# jdds-arduino.net
KiCad netlist of a schematic drawn in EAGLE
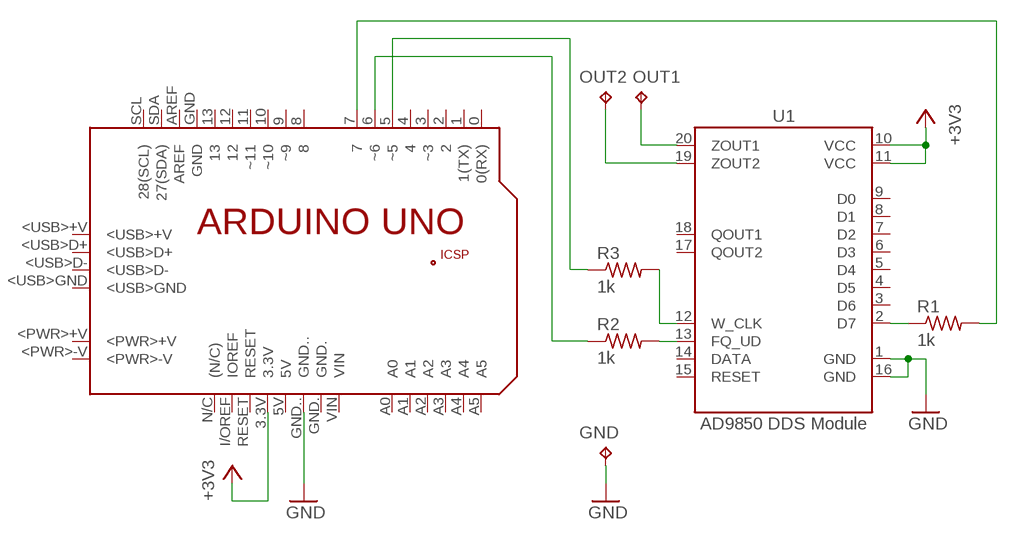
[diagram p0: schematic, sheet 1]

(export (version "E")
  (design (tool "Eeschema 10.0.6"))
  (components
    (comp (ref "GND")
      (value "TPPAD1-20")
      (footprint "eagle-import:P1-20")
      (libsource (lib "eagle-import") (part "TPPAD1-20"))
    )
    (comp (ref "OUT1")
      (value "TPPAD1-20")
      (footprint "eagle-import:P1-20")
      (libsource (lib "eagle-import") (part "TPPAD1-20"))
    )
    (comp (ref "OUT2")
      (value "TPPAD1-20")
      (footprint "eagle-import:P1-20")
      (libsource (lib "eagle-import") (part "TPPAD1-20"))
    )
    (comp (ref "PCB1")
      (value "ARDUINO_UNO")
      (footprint "eagle-import:ARDUINO_UNO")
      (libsource (lib "eagle-import") (part "ARDUINO_UNO"))
    )
    (comp (ref "R1")
      (value "1k")
      (footprint "eagle-import:0207_10")
      (libsource (lib "eagle-import") (part "R-US_0207/10"))
    )
    (comp (ref "R2")
      (value "1k")
      (footprint "eagle-import:0207_10")
      (libsource (lib "eagle-import") (part "R-US_0207/10"))
    )
    (comp (ref "R3")
      (value "1k")
      (footprint "eagle-import:0207_10")
      (libsource (lib "eagle-import") (part "R-US_0207/10"))
    )
    (comp (ref "U1")
      (value "AD9850 DDS Module")
      (footprint "eagle-import:DDS_AD9850")
      (libsource (lib "eagle-import") (part "DDS_MODULE{colon}AD9850DDS_MODULE"))
    )
  )
  (nets
    (net (code "1") (name "+3V3") (class "Default")
      (node (ref "PCB1") (pin "3.3V") (pinfunction "3.3V_3.3V") (pintype "bidirectional"))
      (node (ref "U1") (pin "10") (pinfunction "VCC_10") (pintype "power_in"))
      (node (ref "U1") (pin "11") (pinfunction "VCC_11") (pintype "power_in"))
    )
    (net (code "2") (name "GND") (class "Default")
      (node (ref "GND") (pin "TP") (pinfunction "TP_TP") (pintype "input"))
      (node (ref "PCB1") (pin "GND..") (pinfunction "GND.._GND..") (pintype "bidirectional"))
      (node (ref "U1") (pin "1") (pinfunction "GND_1") (pintype "power_in"))
      (node (ref "U1") (pin "16") (pinfunction "GND_16") (pintype "power_in"))
    )
    (net (code "3") (name "Net-(PCB1-Pad7)") (class "Default")
      (node (ref "PCB1") (pin "7") (pinfunction "7_7") (pintype "bidirectional"))
      (node (ref "R1") (pin "2") (pinfunction "2_2") (pintype "passive"))
    )
    (net (code "4") (name "Net-(PCB1-~{5})") (class "Default")
      (node (ref "PCB1") (pin "5") (pinfunction "~{5}_5") (pintype "bidirectional"))
      (node (ref "R3") (pin "1") (pinfunction "1_1") (pintype "passive"))
    )
    (net (code "5") (name "Net-(PCB1-~{6})") (class "Default")
      (node (ref "PCB1") (pin "6") (pinfunction "~{6}_6") (pintype "bidirectional"))
      (node (ref "R2") (pin "1") (pinfunction "1_1") (pintype "passive"))
    )
    (net (code "6") (name "Net-(U1-D7)") (class "Default")
      (node (ref "R1") (pin "1") (pinfunction "1_1") (pintype "passive"))
      (node (ref "U1") (pin "2") (pinfunction "D7_2") (pintype "input"))
    )
    (net (code "7") (name "Net-(U1-FQ_UD)") (class "Default")
      (node (ref "R2") (pin "2") (pinfunction "2_2") (pintype "passive"))
      (node (ref "U1") (pin "13") (pinfunction "FQ_UD_13") (pintype "input"))
    )
    (net (code "8") (name "Net-(U1-W_CLK)") (class "Default")
      (node (ref "R3") (pin "2") (pinfunction "2_2") (pintype "passive"))
      (node (ref "U1") (pin "12") (pinfunction "W_CLK_12") (pintype "input"))
    )
    (net (code "9") (name "Net-(U1-ZOUT1)") (class "Default")
      (node (ref "OUT1") (pin "TP") (pinfunction "TP_TP") (pintype "input"))
      (node (ref "U1") (pin "20") (pinfunction "ZOUT1_20") (pintype "output"))
    )
    (net (code "10") (name "Net-(U1-ZOUT2)") (class "Default")
      (node (ref "OUT2") (pin "TP") (pinfunction "TP_TP") (pintype "input"))
      (node (ref "U1") (pin "19") (pinfunction "ZOUT2_19") (pintype "output"))
    )
    (net (code "11") (name "unconnected-(PCB1-(N{slash}C)-PadN{slash}C)") (class "Default")
      (node (ref "PCB1") (pin "N/C") (pinfunction "(N/C)_N/C") (pintype "bidirectional"))
    )
    (net (code "12") (name "unconnected-(PCB1-0(RX)-Pad0)") (class "Default")
      (node (ref "PCB1") (pin "0") (pinfunction "0(RX)_0") (pintype "bidirectional"))
    )
    (net (code "13") (name "unconnected-(PCB1-1(TX)-Pad1)") (class "Default")
      (node (ref "PCB1") (pin "1") (pinfunction "1(TX)_1") (pintype "bidirectional"))
    )
    (net (code "14") (name "unconnected-(PCB1-27(SDA)-PadSDA)") (class "Default")
      (node (ref "PCB1") (pin "SDA") (pinfunction "27(SDA)_SDA") (pintype "bidirectional"))
    )
    (net (code "15") (name "unconnected-(PCB1-28(SCL)-PadSCL)") (class "Default")
      (node (ref "PCB1") (pin "SCL") (pinfunction "28(SCL)_SCL") (pintype "bidirectional"))
    )
    (net (code "16") (name "unconnected-(PCB1-IOREF-PadI{slash}OREF)") (class "Default")
      (node (ref "PCB1") (pin "I/OREF") (pinfunction "IOREF_I/OREF") (pintype "bidirectional"))
    )
    (net (code "17") (name "unconnected-(PCB1-Pad+5V)") (class "Default")
      (node (ref "PCB1") (pin "+5V") (pinfunction "+5V_+5V") (pintype "bidirectional"))
    )
    (net (code "18") (name "unconnected-(PCB1-Pad2)") (class "Default")
      (node (ref "PCB1") (pin "2") (pinfunction "2_2") (pintype "bidirectional"))
    )
    (net (code "19") (name "unconnected-(PCB1-Pad4)") (class "Default")
      (node (ref "PCB1") (pin "4") (pinfunction "4_4") (pintype "bidirectional"))
    )
    (net (code "20") (name "unconnected-(PCB1-Pad5V)") (class "Default")
      (node (ref "PCB1") (pin "5V") (pinfunction "5V_5V") (pintype "bidirectional"))
    )
    (net (code "21") (name "unconnected-(PCB1-Pad8)") (class "Default")
      (node (ref "PCB1") (pin "8") (pinfunction "8_8") (pintype "bidirectional"))
    )
    (net (code "22") (name "unconnected-(PCB1-Pad12)") (class "Default")
      (node (ref "PCB1") (pin "12") (pinfunction "12_12") (pintype "bidirectional"))
    )
    (net (code "23") (name "unconnected-(PCB1-Pad13)") (class "Default")
      (node (ref "PCB1") (pin "13") (pinfunction "13_13") (pintype "bidirectional"))
    )
    (net (code "24") (name "unconnected-(PCB1-Pad<PWR>+V)") (class "Default")
      (node (ref "PCB1") (pin "<PWR>+V") (pinfunction "<PWR>+V_<PWR>+V") (pintype "bidirectional"))
    )
    (net (code "25") (name "unconnected-(PCB1-Pad<PWR>-V)") (class "Default")
      (node (ref "PCB1") (pin "<PWR>-V") (pinfunction "<PWR>-V_<PWR>-V") (pintype "bidirectional"))
    )
    (net (code "26") (name "unconnected-(PCB1-Pad<USB>+V)") (class "Default")
      (node (ref "PCB1") (pin "<USB>+V") (pinfunction "<USB>+V_<USB>+V") (pintype "bidirectional"))
    )
    (net (code "27") (name "unconnected-(PCB1-Pad<USB>D+)") (class "Default")
      (node (ref "PCB1") (pin "<USB>D+") (pinfunction "<USB>D+_<USB>D+") (pintype "bidirectional"))
    )
    (net (code "28") (name "unconnected-(PCB1-Pad<USB>D-)") (class "Default")
      (node (ref "PCB1") (pin "<USB>D-") (pinfunction "<USB>D-_<USB>D-") (pintype "bidirectional"))
    )
    (net (code "29") (name "unconnected-(PCB1-Pad<USB>GND)") (class "Default")
      (node (ref "PCB1") (pin "<USB>GND") (pinfunction "<USB>GND_<USB>GND") (pintype "bidirectional"))
    )
    (net (code "30") (name "unconnected-(PCB1-PadA0)") (class "Default")
      (node (ref "PCB1") (pin "A0") (pinfunction "A0_A0") (pintype "bidirectional"))
    )
    (net (code "31") (name "unconnected-(PCB1-PadA1)") (class "Default")
      (node (ref "PCB1") (pin "A1") (pinfunction "A1_A1") (pintype "bidirectional"))
    )
    (net (code "32") (name "unconnected-(PCB1-PadA2)") (class "Default")
      (node (ref "PCB1") (pin "A2") (pinfunction "A2_A2") (pintype "bidirectional"))
    )
    (net (code "33") (name "unconnected-(PCB1-PadA3)") (class "Default")
      (node (ref "PCB1") (pin "A3") (pinfunction "A3_A3") (pintype "bidirectional"))
    )
    (net (code "34") (name "unconnected-(PCB1-PadA4)") (class "Default")
      (node (ref "PCB1") (pin "A4") (pinfunction "A4_A4") (pintype "bidirectional"))
    )
    (net (code "35") (name "unconnected-(PCB1-PadA5)") (class "Default")
      (node (ref "PCB1") (pin "A5") (pinfunction "A5_A5") (pintype "bidirectional"))
    )
    (net (code "36") (name "unconnected-(PCB1-PadAREF)") (class "Default")
      (node (ref "PCB1") (pin "AREF") (pinfunction "AREF_AREF") (pintype "bidirectional"))
    )
    (net (code "37") (name "unconnected-(PCB1-PadGND)") (class "Default")
      (node (ref "PCB1") (pin "GND") (pinfunction "GND_GND") (pintype "bidirectional"))
    )
    (net (code "38") (name "unconnected-(PCB1-PadGND.)") (class "Default")
      (node (ref "PCB1") (pin "GND.") (pinfunction "GND._GND.") (pintype "bidirectional"))
    )
    (net (code "39") (name "unconnected-(PCB1-PadGND_)") (class "Default")
      (node (ref "PCB1") (pin "GND_") (pinfunction "GND__GND_") (pintype "bidirectional"))
    )
    (net (code "40") (name "unconnected-(PCB1-PadMISO)") (class "Default")
      (node (ref "PCB1") (pin "MISO") (pinfunction "MISO_MISO") (pintype "bidirectional"))
    )
    (net (code "41") (name "unconnected-(PCB1-PadMOSI)") (class "Default")
      (node (ref "PCB1") (pin "MOSI") (pinfunction "MOSI_MOSI") (pintype "bidirectional"))
    )
    (net (code "42") (name "unconnected-(PCB1-PadRESET)") (class "Default")
      (node (ref "PCB1") (pin "RESET") (pinfunction "RESET_RESET") (pintype "bidirectional"))
    )
    (net (code "43") (name "unconnected-(PCB1-PadRESET.)") (class "Default")
      (node (ref "PCB1") (pin "RESET.") (pinfunction "RESET._RESET.") (pintype "bidirectional"))
    )
    (net (code "44") (name "unconnected-(PCB1-PadSCK)") (class "Default")
      (node (ref "PCB1") (pin "SCK") (pinfunction "SCK_SCK") (pintype "bidirectional"))
    )
    (net (code "45") (name "unconnected-(PCB1-PadVIN)") (class "Default")
      (node (ref "PCB1") (pin "VIN") (pinfunction "VIN_VIN") (pintype "bidirectional"))
    )
    (net (code "46") (name "unconnected-(PCB1-~{3}-Pad3)") (class "Default")
      (node (ref "PCB1") (pin "3") (pinfunction "~{3}_3") (pintype "bidirectional"))
    )
    (net (code "47") (name "unconnected-(PCB1-~{9}-Pad9)") (class "Default")
      (node (ref "PCB1") (pin "9") (pinfunction "~{9}_9") (pintype "bidirectional"))
    )
    (net (code "48") (name "unconnected-(PCB1-~{10}-Pad10)") (class "Default")
      (node (ref "PCB1") (pin "10") (pinfunction "~{10}_10") (pintype "bidirectional"))
    )
    (net (code "49") (name "unconnected-(PCB1-~{11}-Pad11)") (class "Default")
      (node (ref "PCB1") (pin "11") (pinfunction "~{11}_11") (pintype "bidirectional"))
    )
    (net (code "50") (name "unconnected-(U1-D0-Pad9)") (class "Default")
      (node (ref "U1") (pin "9") (pinfunction "D0_9") (pintype "input"))
    )
    (net (code "51") (name "unconnected-(U1-D1-Pad8)") (class "Default")
      (node (ref "U1") (pin "8") (pinfunction "D1_8") (pintype "input"))
    )
    (net (code "52") (name "unconnected-(U1-D2-Pad7)") (class "Default")
      (node (ref "U1") (pin "7") (pinfunction "D2_7") (pintype "input"))
    )
    (net (code "53") (name "unconnected-(U1-D3-Pad6)") (class "Default")
      (node (ref "U1") (pin "6") (pinfunction "D3_6") (pintype "input"))
    )
    (net (code "54") (name "unconnected-(U1-D4-Pad5)") (class "Default")
      (node (ref "U1") (pin "5") (pinfunction "D4_5") (pintype "input"))
    )
    (net (code "55") (name "unconnected-(U1-D5-Pad4)") (class "Default")
      (node (ref "U1") (pin "4") (pinfunction "D5_4") (pintype "input"))
    )
    (net (code "56") (name "unconnected-(U1-D6-Pad3)") (class "Default")
      (node (ref "U1") (pin "3") (pinfunction "D6_3") (pintype "input"))
    )
    (net (code "57") (name "unconnected-(U1-DATA-Pad14)") (class "Default")
      (node (ref "U1") (pin "14") (pinfunction "DATA_14") (pintype "input"))
    )
    (net (code "58") (name "unconnected-(U1-QOUT1-Pad18)") (class "Default")
      (node (ref "U1") (pin "18") (pinfunction "QOUT1_18") (pintype "output"))
    )
    (net (code "59") (name "unconnected-(U1-QOUT2-Pad17)") (class "Default")
      (node (ref "U1") (pin "17") (pinfunction "QOUT2_17") (pintype "output"))
    )
    (net (code "60") (name "unconnected-(U1-RESET-Pad15)") (class "Default")
      (node (ref "U1") (pin "15") (pinfunction "RESET_15") (pintype "bidirectional"))
    )
  )
)
